# WaveSch.net
KiCad netlist of a schematic drawn in Altium Designer
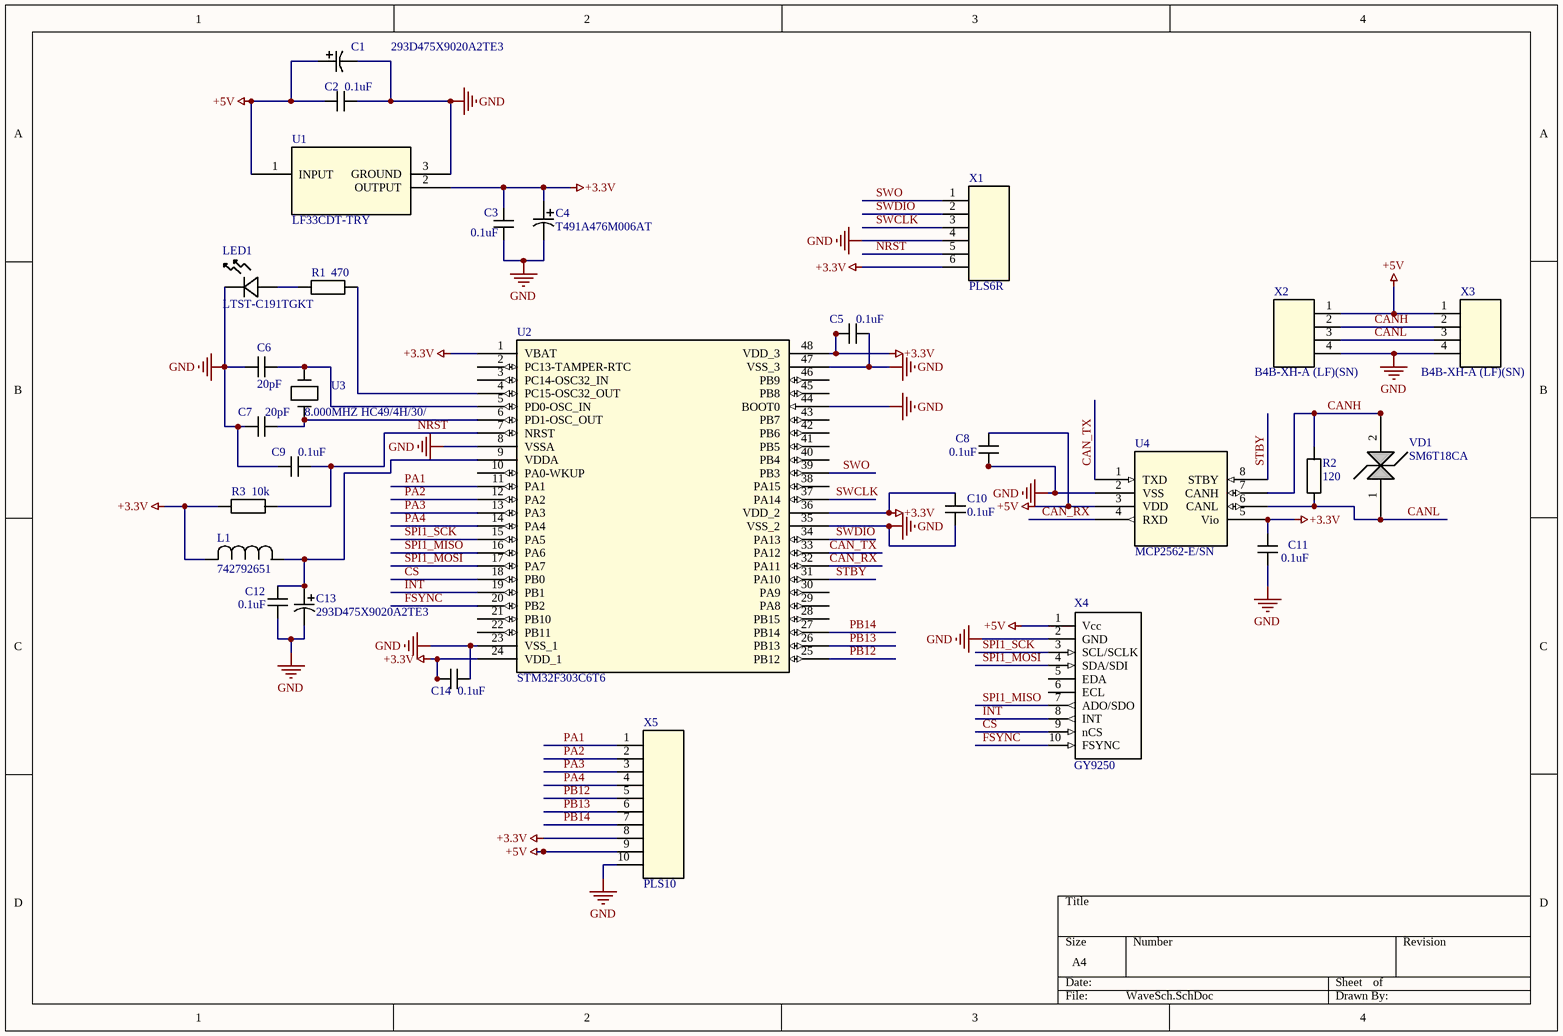
[diagram p0: WaveSch.SchDoc]

(export (version "E")
  (design (tool "Eeschema 10.0.6"))
  (components
    (comp (ref "C1")
      (value "293D475X9020A2TE3")
      (footprint "CAPT3216N_KEM")
      (description "No Description Available")
      (fields
        (field (name "MANUFACTURER_PART_NUMBER") "T491A476M006AT")
        (field (name "COPYRIGHT") "Copyright (C) 2018 Accelerated Designs. All rights reserved")
      )
      (libsource (lib "T491A476M006AT") (part "T491A476M006AT"))
    )
    (comp (ref "C2")
      (value "0.1uF")
      (footprint "0603-L")
      (description "No Description Available")
      (fields
        (field (name "MANUFACTURER_PART_NUMBER") "0603ZC224JAT2A")
        (field (name "COPYRIGHT") "Copyright (C) 2018 Accelerated Designs. All rights reserved")
      )
      (libsource (lib "Cap0603") (part "0603ZC224JAT2A"))
    )
    (comp (ref "C3")
      (value "0.1uF")
      (footprint "0603-L")
      (description "No Description Available")
      (fields
        (field (name "MANUFACTURER_PART_NUMBER") "0603ZC224JAT2A")
        (field (name "COPYRIGHT") "Copyright (C) 2018 Accelerated Designs. All rights reserved")
      )
      (libsource (lib "Cap0603") (part "0603ZC224JAT2A"))
    )
    (comp (ref "C4")
      (value "T491A476M006AT")
      (footprint "CAPT3216N_KEM")
      (description "No Description Available")
      (fields (field (name "COPYRIGHT") "Copyright (C) 2018 Accelerated Designs. All rights reserved"))
      (libsource (lib "T491A476M006AT") (part "T491A476M006AT"))
    )
    (comp (ref "C5")
      (value "0.1uF")
      (footprint "0603-L")
      (description "No Description Available")
      (fields
        (field (name "MANUFACTURER_PART_NUMBER") "0603ZC224JAT2A")
        (field (name "COPYRIGHT") "Copyright (C) 2018 Accelerated Designs. All rights reserved")
      )
      (libsource (lib "Cap0603") (part "0603ZC224JAT2A"))
    )
    (comp (ref "C6")
      (value "20pF")
      (footprint "0603-L")
      (description "No Description Available")
      (fields
        (field (name "MANUFACTURER_PART_NUMBER") "0603ZC224JAT2A")
        (field (name "COPYRIGHT") "Copyright (C) 2018 Accelerated Designs. All rights reserved")
      )
      (libsource (lib "Cap0603") (part "0603ZC224JAT2A"))
    )
    (comp (ref "C7")
      (value "20pF")
      (footprint "0603-L")
      (description "No Description Available")
      (fields
        (field (name "MANUFACTURER_PART_NUMBER") "0603ZC224JAT2A")
        (field (name "COPYRIGHT") "Copyright (C) 2018 Accelerated Designs. All rights reserved")
      )
      (libsource (lib "Cap0603") (part "0603ZC224JAT2A"))
    )
    (comp (ref "C8")
      (value "0.1uF")
      (footprint "0603-L")
      (description "No Description Available")
      (fields
        (field (name "MANUFACTURER_PART_NUMBER") "0603ZC224JAT2A")
        (field (name "COPYRIGHT") "Copyright (C) 2018 Accelerated Designs. All rights reserved")
      )
      (libsource (lib "Cap0603") (part "0603ZC224JAT2A"))
    )
    (comp (ref "C9")
      (value "0.1uF")
      (footprint "0603-L")
      (description "No Description Available")
      (fields
        (field (name "MANUFACTURER_PART_NUMBER") "0603ZC224JAT2A")
        (field (name "COPYRIGHT") "Copyright (C) 2018 Accelerated Designs. All rights reserved")
      )
      (libsource (lib "Cap0603") (part "0603ZC224JAT2A"))
    )
    (comp (ref "C10")
      (value "0.1uF")
      (footprint "0603-L")
      (description "No Description Available")
      (fields
        (field (name "MANUFACTURER_PART_NUMBER") "0603ZC224JAT2A")
        (field (name "COPYRIGHT") "Copyright (C) 2018 Accelerated Designs. All rights reserved")
      )
      (libsource (lib "Cap0603") (part "0603ZC224JAT2A"))
    )
    (comp (ref "C11")
      (value "0.1uF")
      (footprint "0603-L")
      (description "No Description Available")
      (fields
        (field (name "MANUFACTURER_PART_NUMBER") "0603ZC224JAT2A")
        (field (name "COPYRIGHT") "Copyright (C) 2018 Accelerated Designs. All rights reserved")
      )
      (libsource (lib "Cap0603") (part "0603ZC224JAT2A"))
    )
    (comp (ref "C12")
      (value "0.1uF")
      (footprint "0603-L")
      (description "No Description Available")
      (fields
        (field (name "MANUFACTURER_PART_NUMBER") "0603ZC224JAT2A")
        (field (name "COPYRIGHT") "Copyright (C) 2018 Accelerated Designs. All rights reserved")
      )
      (libsource (lib "Cap0603") (part "0603ZC224JAT2A"))
    )
    (comp (ref "C13")
      (value "293D475X9020A2TE3")
      (footprint "CAPT3216N_KEM")
      (description "No Description Available")
      (fields
        (field (name "MANUFACTURER_PART_NUMBER") "T491A476M006AT")
        (field (name "COPYRIGHT") "Copyright (C) 2018 Accelerated Designs. All rights reserved")
      )
      (libsource (lib "T491A476M006AT") (part "T491A476M006AT"))
    )
    (comp (ref "C14")
      (value "0.1uF")
      (footprint "0603-L")
      (description "No Description Available")
      (fields
        (field (name "MANUFACTURER_PART_NUMBER") "0603ZC224JAT2A")
        (field (name "COPYRIGHT") "Copyright (C) 2018 Accelerated Designs. All rights reserved")
      )
      (libsource (lib "Cap0603") (part "0603ZC224JAT2A"))
    )
    (comp (ref "L1")
      (value "742792651")
      (footprint "IND_BLM18_0603")
      (description "No Description Available")
      (fields
        (field (name "MANUFACTURER_PART_NUMBER") "BLM18BB331SN1D")
        (field (name "COPYRIGHT") "Copyright (C) 2018 Accelerated Designs. All rights reserved")
      )
      (libsource (lib "742792651") (part "BLM18BB331SN1D"))
    )
    (comp (ref "LED1")
      (value "LTST-C191TGKT")
      (footprint "LED_LTW-C193TS5_")
      (description "No Description Available")
      (fields (field (name "COPYRIGHT") "Copyright (C) 2016 Accelerated Designs. All rights reserved"))
      (libsource (lib "LTST-C191TGKT") (part "LTST-C191TGKT"))
    )
    (comp (ref "R1")
      (value "470")
      (footprint "RC0603N")
      (description "No Description Available")
      (fields
        (field (name "MANUFACTURER_PART_NUMBER") "ERA-3AEB101V")
        (field (name "COPYRIGHT") "Copyright (C) 2018 Accelerated Designs. All rights reserved")
      )
      (libsource (lib "Res0603") (part "ERA-3AEB101V"))
    )
    (comp (ref "R2")
      (value "120")
      (footprint "RC0603N")
      (description "No Description Available")
      (fields
        (field (name "MANUFACTURER_PART_NUMBER") "ERA-3AEB101V")
        (field (name "COPYRIGHT") "Copyright (C) 2018 Accelerated Designs. All rights reserved")
      )
      (libsource (lib "Res0603") (part "ERA-3AEB101V"))
    )
    (comp (ref "R3")
      (value "10k")
      (footprint "RC0603N")
      (description "No Description Available")
      (fields
        (field (name "MANUFACTURER_PART_NUMBER") "ERA-3AEB101V")
        (field (name "COPYRIGHT") "Copyright (C) 2018 Accelerated Designs. All rights reserved")
      )
      (libsource (lib "Res0603") (part "ERA-3AEB101V"))
    )
    (comp (ref "U1")
      (value "LF33CDT-TRY")
      (footprint "DPAK_STM")
      (description "No Description Available")
      (fields (field (name "COPYRIGHT") "Copyright (C) 2018 Accelerated Designs. All rights reserved"))
      (libsource (lib "LF33CDT") (part "LF33CDT-TRY"))
    )
    (comp (ref "U2")
      (value "STM32F303C6T6")
      (footprint "LQFP-48_STM")
      (description "No Description Available")
      (fields
        (field (name "MANUFACTURER_PART_NUMBER") "STM32F303CBT6")
        (field (name "COPYRIGHT") "Copyright (C) 2018 Accelerated Designs. All rights reserved")
      )
      (libsource (lib "STM32F303CB") (part "STM32F303CCT6"))
    )
    (comp (ref "U3")
      (value "8.000MHZ HC49/4H/30/")
      (footprint "HC49-4H")
      (description "No Description Available")
      (fields (field (name "COPYRIGHT") "Copyright (C) 2018 Accelerated Designs. All rights reserved"))
      (libsource (lib "QuartzThrough") (part "8.000MHZ HC49/4H"))
    )
    (comp (ref "U4")
      (value "MCP2562-E/SN")
      (footprint "SOIC8-N_MC_MCH")
      (description "No Description Available")
      (fields
        (field (name "MANUFACTURER_PART_NUMBER") "MCP2562FD-E/SN")
        (field (name "COPYRIGHT") "Copyright (C) 2018 Accelerated Designs. All rights reserved")
      )
      (libsource (lib "MCP2561FD-ESN") (part "MCP2562FD-E/SN"))
    )
    (comp (ref "VD1")
      (value "SM6T18CA")
      (footprint "SMB_STM")
      (description "No Description Available")
      (fields
        (field (name "MANUFACTURER_PART_NUMBER") "LXES1UTAA1-157")
        (field (name "COPYRIGHT") "Copyright (C) 2018 Accelerated Designs. All rights reserved")
      )
      (libsource (lib "SM6T18CA") (part "SM6T18CA"))
    )
    (comp (ref "X1")
      (value "PLS6R")
      (footprint "PLS-6R")
      (description "No Description Available")
      (fields (field (name "COPYRIGHT") "Copyright (C) 2018 Accelerated Designs. All rights reserved"))
      (libsource (lib "PLS6R") (part "PLS6R"))
    )
    (comp (ref "X2")
      (value "B4B-XH-A (LF)(SN)")
      (footprint "CONN_B4B-XH-A (L")
      (description "No Description Available")
      (fields (field (name "COPYRIGHT") "Copyright (C) 2018 Accelerated Designs. All rights reserved"))
      (libsource (lib "B4B") (part "B4B-XH-A (LF)(SN"))
    )
    (comp (ref "X3")
      (value "B4B-XH-A (LF)(SN)")
      (footprint "CONN_B4B-XH-A (L")
      (description "No Description Available")
      (fields (field (name "COPYRIGHT") "Copyright (C) 2018 Accelerated Designs. All rights reserved"))
      (libsource (lib "") (part "B4B-XH-A (LF)(SN_1"))
    )
    (comp (ref "X4") (value "GY9250") (footprint "GY9250") (libsource (lib "Schlib1") (part "GY9250")))
    (comp (ref "X5")
      (value "PLS10")
      (footprint "PLS-8")
      (description "No Description Available")
      (fields (field (name "COPYRIGHT") "Copyright (C) 2018 Accelerated Designs. All rights reserved"))
      (libsource (lib "PLS10") (part "PLS6R"))
    )
  )
  (nets
    (net (code "1") (name "+3.3V") (class "Default")
      (node (ref "C10") (pin "2") (pinfunction "2_2") (pintype "passive"))
      (node (ref "C11") (pin "2") (pinfunction "2_2") (pintype "passive"))
      (node (ref "C14") (pin "1") (pinfunction "1_1") (pintype "passive"))
      (node (ref "C3") (pin "2") (pinfunction "2_2") (pintype "passive"))
      (node (ref "C4") (pin "1") (pinfunction "1_1") (pintype "passive"))
      (node (ref "C5") (pin "1") (pinfunction "1_1") (pintype "passive"))
      (node (ref "L1") (pin "2") (pinfunction "2_2") (pintype "passive"))
      (node (ref "R3") (pin "2") (pinfunction "2_2") (pintype "passive"))
      (node (ref "U1") (pin "2") (pinfunction "OUTPUT_2") (pintype "passive"))
      (node (ref "U2") (pin "1") (pinfunction "VBAT_1") (pintype "power_in"))
      (node (ref "U2") (pin "24") (pinfunction "VDD_1_24") (pintype "power_in"))
      (node (ref "U2") (pin "36") (pinfunction "VDD_2_36") (pintype "power_in"))
      (node (ref "U2") (pin "48") (pinfunction "VDD_3_48") (pintype "power_in"))
      (node (ref "U4") (pin "5") (pinfunction "Vio_5") (pintype "passive"))
      (node (ref "X1") (pin "6") (pinfunction "6_6") (pintype "passive"))
      (node (ref "X5") (pin "8") (pinfunction "8_8") (pintype "passive"))
    )
    (net (code "2") (name "+5V") (class "Default")
      (node (ref "C1") (pin "1") (pinfunction "1_1") (pintype "passive"))
      (node (ref "C2") (pin "2") (pinfunction "2_2") (pintype "passive"))
      (node (ref "C8") (pin "2") (pinfunction "2_2") (pintype "passive"))
      (node (ref "U1") (pin "1") (pinfunction "INPUT_1") (pintype "passive"))
      (node (ref "U4") (pin "3") (pinfunction "VDD_3") (pintype "power_in"))
      (node (ref "X2") (pin "1") (pinfunction "1_1") (pintype "passive"))
      (node (ref "X3") (pin "1") (pinfunction "1_1") (pintype "passive"))
      (node (ref "X4") (pin "1") (pinfunction "Vcc_1") (pintype "power_in"))
      (node (ref "X5") (pin "9") (pinfunction "9_9") (pintype "passive"))
    )
    (net (code "3") (name "/CANH") (class "Default")
      (node (ref "R2") (pin "1") (pinfunction "1_1") (pintype "passive"))
      (node (ref "U4") (pin "7") (pinfunction "CANH_7") (pintype "bidirectional"))
      (node (ref "VD1") (pin "2") (pinfunction "ANODE_2") (pintype "passive"))
      (node (ref "X2") (pin "2") (pinfunction "2_2") (pintype "passive"))
      (node (ref "X3") (pin "2") (pinfunction "2_2") (pintype "passive"))
    )
    (net (code "4") (name "/CANL") (class "Default")
      (node (ref "R2") (pin "2") (pinfunction "2_2") (pintype "passive"))
      (node (ref "U4") (pin "6") (pinfunction "CANL_6") (pintype "bidirectional"))
      (node (ref "VD1") (pin "1") (pinfunction "CATHODE_1") (pintype "passive"))
      (node (ref "X2") (pin "3") (pinfunction "3_3") (pintype "passive"))
      (node (ref "X3") (pin "3") (pinfunction "3_3") (pintype "passive"))
    )
    (net (code "5") (name "/CAN_RX") (class "Default")
      (node (ref "U2") (pin "32") (pinfunction "PA11_32") (pintype "bidirectional"))
      (node (ref "U4") (pin "4") (pinfunction "RXD_4") (pintype "output"))
    )
    (net (code "6") (name "/CAN_TX") (class "Default")
      (node (ref "U2") (pin "33") (pinfunction "PA12_33") (pintype "bidirectional"))
      (node (ref "U4") (pin "1") (pinfunction "TXD_1") (pintype "input"))
    )
    (net (code "7") (name "/CS") (class "Default")
      (node (ref "U2") (pin "18") (pinfunction "PB0_18") (pintype "bidirectional"))
      (node (ref "X4") (pin "9") (pinfunction "nCS_9") (pintype "input"))
    )
    (net (code "8") (name "/FSYNC") (class "Default")
      (node (ref "U2") (pin "20") (pinfunction "PB2_20") (pintype "bidirectional"))
      (node (ref "X4") (pin "10") (pinfunction "FSYNC_10") (pintype "input"))
    )
    (net (code "9") (name "/INT") (class "Default")
      (node (ref "U2") (pin "19") (pinfunction "PB1_19") (pintype "bidirectional"))
      (node (ref "X4") (pin "8") (pinfunction "INT_8") (pintype "output"))
    )
    (net (code "10") (name "/NRST") (class "Default")
      (node (ref "C9") (pin "2") (pinfunction "2_2") (pintype "passive"))
      (node (ref "R3") (pin "1") (pinfunction "1_1") (pintype "passive"))
      (node (ref "U2") (pin "7") (pinfunction "NRST_7") (pintype "bidirectional"))
      (node (ref "X1") (pin "5") (pinfunction "5_5") (pintype "passive"))
    )
    (net (code "11") (name "/PA1") (class "Default")
      (node (ref "U2") (pin "11") (pinfunction "PA1_11") (pintype "bidirectional"))
      (node (ref "X5") (pin "1") (pinfunction "1_1") (pintype "passive"))
    )
    (net (code "12") (name "/PA2") (class "Default")
      (node (ref "U2") (pin "12") (pinfunction "PA2_12") (pintype "bidirectional"))
      (node (ref "X5") (pin "2") (pinfunction "2_2") (pintype "passive"))
    )
    (net (code "13") (name "/PA3") (class "Default")
      (node (ref "U2") (pin "13") (pinfunction "PA3_13") (pintype "bidirectional"))
      (node (ref "X5") (pin "3") (pinfunction "3_3") (pintype "passive"))
    )
    (net (code "14") (name "/PA4") (class "Default")
      (node (ref "U2") (pin "14") (pinfunction "PA4_14") (pintype "bidirectional"))
      (node (ref "X5") (pin "4") (pinfunction "4_4") (pintype "passive"))
    )
    (net (code "15") (name "/PB12") (class "Default")
      (node (ref "U2") (pin "25") (pinfunction "PB12_25") (pintype "bidirectional"))
      (node (ref "X5") (pin "5") (pinfunction "5_5") (pintype "passive"))
    )
    (net (code "16") (name "/PB13") (class "Default")
      (node (ref "U2") (pin "26") (pinfunction "PB13_26") (pintype "bidirectional"))
      (node (ref "X5") (pin "6") (pinfunction "6_6") (pintype "passive"))
    )
    (net (code "17") (name "/PB14") (class "Default")
      (node (ref "U2") (pin "27") (pinfunction "PB14_27") (pintype "bidirectional"))
      (node (ref "X5") (pin "7") (pinfunction "7_7") (pintype "passive"))
    )
    (net (code "18") (name "/SPI1_MISO") (class "Default")
      (node (ref "U2") (pin "16") (pinfunction "PA6_16") (pintype "bidirectional"))
      (node (ref "X4") (pin "7") (pinfunction "ADO/SDO_7") (pintype "output"))
    )
    (net (code "19") (name "/SPI1_MOSI") (class "Default")
      (node (ref "U2") (pin "17") (pinfunction "PA7_17") (pintype "bidirectional"))
      (node (ref "X4") (pin "4") (pinfunction "SDA/SDI_4") (pintype "input"))
    )
    (net (code "20") (name "/SPI1_SCK") (class "Default")
      (node (ref "U2") (pin "15") (pinfunction "PA5_15") (pintype "bidirectional"))
      (node (ref "X4") (pin "3") (pinfunction "SCL/SCLK_3") (pintype "input"))
    )
    (net (code "21") (name "/STBY") (class "Default")
      (node (ref "U2") (pin "31") (pinfunction "PA10_31") (pintype "bidirectional"))
      (node (ref "U4") (pin "8") (pinfunction "STBY_8") (pintype "input"))
    )
    (net (code "22") (name "/SWCLK") (class "Default")
      (node (ref "U2") (pin "37") (pinfunction "PA14_37") (pintype "bidirectional"))
      (node (ref "X1") (pin "3") (pinfunction "3_3") (pintype "passive"))
    )
    (net (code "23") (name "/SWDIO") (class "Default")
      (node (ref "U2") (pin "34") (pinfunction "PA13_34") (pintype "bidirectional"))
      (node (ref "X1") (pin "2") (pinfunction "2_2") (pintype "passive"))
    )
    (net (code "24") (name "/SWO") (class "Default")
      (node (ref "U2") (pin "39") (pinfunction "PB3_39") (pintype "bidirectional"))
      (node (ref "X1") (pin "1") (pinfunction "1_1") (pintype "passive"))
    )
    (net (code "25") (name "GND") (class "Default")
      (node (ref "C1") (pin "2") (pinfunction "2_2") (pintype "passive"))
      (node (ref "C10") (pin "1") (pinfunction "1_1") (pintype "passive"))
      (node (ref "C11") (pin "1") (pinfunction "1_1") (pintype "passive"))
      (node (ref "C12") (pin "1") (pinfunction "1_1") (pintype "passive"))
      (node (ref "C13") (pin "2") (pinfunction "2_2") (pintype "passive"))
      (node (ref "C14") (pin "2") (pinfunction "2_2") (pintype "passive"))
      (node (ref "C2") (pin "1") (pinfunction "1_1") (pintype "passive"))
      (node (ref "C3") (pin "1") (pinfunction "1_1") (pintype "passive"))
      (node (ref "C4") (pin "2") (pinfunction "2_2") (pintype "passive"))
      (node (ref "C5") (pin "2") (pinfunction "2_2") (pintype "passive"))
      (node (ref "C6") (pin "1") (pinfunction "1_1") (pintype "passive"))
      (node (ref "C7") (pin "1") (pinfunction "1_1") (pintype "passive"))
      (node (ref "C8") (pin "1") (pinfunction "1_1") (pintype "passive"))
      (node (ref "C9") (pin "1") (pinfunction "1_1") (pintype "passive"))
      (node (ref "LED1") (pin "1") (pinfunction "1_1") (pintype "passive"))
      (node (ref "U1") (pin "3") (pinfunction "GROUND_3") (pintype "passive"))
      (node (ref "U2") (pin "23") (pinfunction "VSS_1_23") (pintype "power_in"))
      (node (ref "U2") (pin "35") (pinfunction "VSS_2_35") (pintype "power_in"))
      (node (ref "U2") (pin "44") (pinfunction "BOOT0_44") (pintype "input"))
      (node (ref "U2") (pin "47") (pinfunction "VSS_3_47") (pintype "power_in"))
      (node (ref "U2") (pin "8") (pinfunction "VSSA_8") (pintype "power_in"))
      (node (ref "U4") (pin "2") (pinfunction "VSS_2") (pintype "power_in"))
      (node (ref "X1") (pin "4") (pinfunction "4_4") (pintype "passive"))
      (node (ref "X2") (pin "4") (pinfunction "4_4") (pintype "passive"))
      (node (ref "X3") (pin "4") (pinfunction "4_4") (pintype "passive"))
      (node (ref "X4") (pin "2") (pinfunction "GND_2") (pintype "power_in"))
      (node (ref "X5") (pin "10") (pinfunction "10_10") (pintype "passive"))
    )
    (net (code "26") (name "Net-(LED1-Pad2)") (class "Default")
      (node (ref "LED1") (pin "2") (pinfunction "2_2") (pintype "passive"))
      (node (ref "R1") (pin "2") (pinfunction "2_2") (pintype "passive"))
    )
    (net (code "27") (name "Net-(U2-PC15-OSC32_OUT)") (class "Default")
      (node (ref "R1") (pin "1") (pinfunction "1_1") (pintype "passive"))
      (node (ref "U2") (pin "4") (pinfunction "PC15-OSC32_OUT_4") (pintype "bidirectional"))
    )
    (net (code "28") (name "Net-(U2-PD0-OSC_IN)") (class "Default")
      (node (ref "C6") (pin "2") (pinfunction "2_2") (pintype "passive"))
      (node (ref "U2") (pin "5") (pinfunction "PD0-OSC_IN_5") (pintype "bidirectional"))
      (node (ref "U3") (pin "2") (pinfunction "2_2") (pintype "passive"))
    )
    (net (code "29") (name "Net-(U2-PD1-OSC_OUT)") (class "Default")
      (node (ref "C7") (pin "2") (pinfunction "2_2") (pintype "passive"))
      (node (ref "U2") (pin "6") (pinfunction "PD1-OSC_OUT_6") (pintype "bidirectional"))
      (node (ref "U3") (pin "1") (pinfunction "1_1") (pintype "passive"))
    )
    (net (code "30") (name "Net-(U2-VDDA)") (class "Default")
      (node (ref "C12") (pin "2") (pinfunction "2_2") (pintype "passive"))
      (node (ref "C13") (pin "1") (pinfunction "1_1") (pintype "passive"))
      (node (ref "L1") (pin "1") (pinfunction "1_1") (pintype "passive"))
      (node (ref "U2") (pin "9") (pinfunction "VDDA_9") (pintype "power_in"))
    )
    (net (code "31") (name "unconnected-(U2-PA0-WKUP-Pad10)") (class "Default")
      (node (ref "U2") (pin "10") (pinfunction "PA0-WKUP_10") (pintype "bidirectional"))
    )
    (net (code "32") (name "unconnected-(U2-PA8-Pad29)") (class "Default")
      (node (ref "U2") (pin "29") (pinfunction "PA8_29") (pintype "bidirectional"))
    )
    (net (code "33") (name "unconnected-(U2-PA9-Pad30)") (class "Default")
      (node (ref "U2") (pin "30") (pinfunction "PA9_30") (pintype "bidirectional"))
    )
    (net (code "34") (name "unconnected-(U2-PA15-Pad38)") (class "Default")
      (node (ref "U2") (pin "38") (pinfunction "PA15_38") (pintype "bidirectional"))
    )
    (net (code "35") (name "unconnected-(U2-PB4-Pad40)") (class "Default")
      (node (ref "U2") (pin "40") (pinfunction "PB4_40") (pintype "bidirectional"))
    )
    (net (code "36") (name "unconnected-(U2-PB5-Pad41)") (class "Default")
      (node (ref "U2") (pin "41") (pinfunction "PB5_41") (pintype "bidirectional"))
    )
    (net (code "37") (name "unconnected-(U2-PB6-Pad42)") (class "Default")
      (node (ref "U2") (pin "42") (pinfunction "PB6_42") (pintype "bidirectional"))
    )
    (net (code "38") (name "unconnected-(U2-PB7-Pad43)") (class "Default")
      (node (ref "U2") (pin "43") (pinfunction "PB7_43") (pintype "bidirectional"))
    )
    (net (code "39") (name "unconnected-(U2-PB8-Pad45)") (class "Default")
      (node (ref "U2") (pin "45") (pinfunction "PB8_45") (pintype "bidirectional"))
    )
    (net (code "40") (name "unconnected-(U2-PB9-Pad46)") (class "Default")
      (node (ref "U2") (pin "46") (pinfunction "PB9_46") (pintype "bidirectional"))
    )
    (net (code "41") (name "unconnected-(U2-PB10-Pad21)") (class "Default")
      (node (ref "U2") (pin "21") (pinfunction "PB10_21") (pintype "bidirectional"))
    )
    (net (code "42") (name "unconnected-(U2-PB11-Pad22)") (class "Default")
      (node (ref "U2") (pin "22") (pinfunction "PB11_22") (pintype "bidirectional"))
    )
    (net (code "43") (name "unconnected-(U2-PB15-Pad28)") (class "Default")
      (node (ref "U2") (pin "28") (pinfunction "PB15_28") (pintype "bidirectional"))
    )
    (net (code "44") (name "unconnected-(U2-PC13-TAMPER-RTC-Pad2)") (class "Default")
      (node (ref "U2") (pin "2") (pinfunction "PC13-TAMPER-RTC_2") (pintype "bidirectional"))
    )
    (net (code "45") (name "unconnected-(U2-PC14-OSC32_IN-Pad3)") (class "Default")
      (node (ref "U2") (pin "3") (pinfunction "PC14-OSC32_IN_3") (pintype "bidirectional"))
    )
    (net (code "46") (name "unconnected-(X4-ECL-Pad6)") (class "Default")
      (node (ref "X4") (pin "6") (pinfunction "ECL_6") (pintype "passive"))
    )
    (net (code "47") (name "unconnected-(X4-EDA-Pad5)") (class "Default")
      (node (ref "X4") (pin "5") (pinfunction "EDA_5") (pintype "passive"))
    )
  )
)
